# Sheet1.net
KiCad netlist of a schematic drawn in Altium Designer
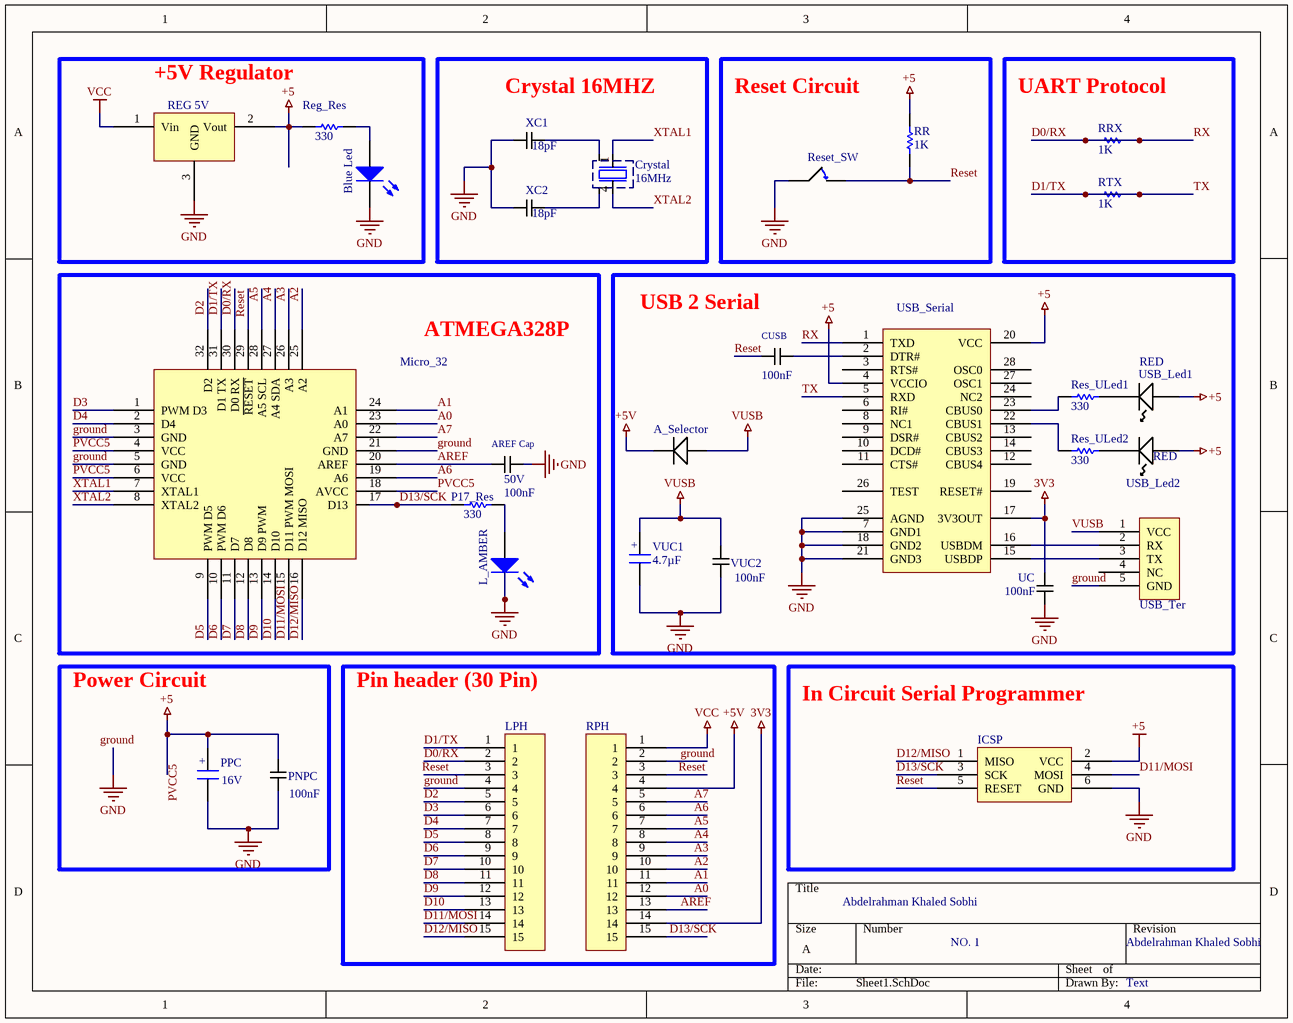
[diagram p0: Sheet1.SchDoc]

(export (version "E")
  (design (tool "Eeschema 10.0.6"))
  (components
    (comp (ref "AREF Cap")
      (value "100nF Ceramic Multilayer Capacitor_1")
      (footprint "CAPCP2012X09N")
      (description "AVX 0805 Standard 100nF Ceramic Multilayer Capacitor, 50 V dc X7R Dielectric ±10% SMD")
      (fields
        (field (name "MANUFACTURER") "AVX")
        (field (name "VOLTAGE") "50V")
        (field (name "CAPACITANCE") "100nF")
        (field (name "CREATOR") "Ritesh Kanjee")
      )
      (libsource (lib "RS Components - Capacitors") (part "100nF Ceramic Multilayer Capacitor_1"))
    )
    (comp (ref "A_Selector")
      (value "Panasonic DB2J20900L Schottky Diode, 0.5A, 20V, 2.4ns, 2-Pin SMini2 F5 B")
      (footprint "DIOM1712X07N")
      (fields
        (field (name "MANUFACTURER") "Panasonic")
        (field (name "MANUFACTURER PART NO.") "DB2J20900L")
        (field (name "CREATED BY") "R Kanjee")
      )
      (libsource (lib "Panasonic Diodes") (part "Schottky Diode, 0.5A, 20V, 2.4ns, 2-Pin SMini2 F5 B"))
    )
    (comp (ref "Blue Led")
      (value "Light-Emitting Diode")
      (libsource (lib "Simulation Generic Components") (part "LED"))
    )
    (comp (ref "Crystal")
      (value "16MHz")
      (footprint "Aker S5C Crystal")
      (description "Aker S5C SMT Crystal")
      (fields
        (field (name "MANUFACTURER") "Aker")
        (field (name "MANUFACTURER PART #") "C5S-16.000-12-3030-X")
        (field (name "CREATOR") "R Kanjee")
      )
      (libsource (lib "Aker Crystals") (part "Aker  C5S-16.000-12-3030-X"))
    )
    (comp (ref "CUSB")
      (value "100nF Ceramic Multilayer Capacitor_1")
      (footprint "CAPCP2012X09N")
      (description "AVX 0805 Standard 100nF Ceramic Multilayer Capacitor, 50 V dc X7R Dielectric ±10% SMD")
      (fields
        (field (name "MANUFACTURER") "AVX")
        (field (name "VOLTAGE") "50V")
        (field (name "CAPACITANCE") "100nF")
        (field (name "CREATOR") "Ritesh Kanjee")
      )
      (libsource (lib "RS Components - Capacitors") (part "100nF Ceramic Multilayer Capacitor_1"))
    )
    (comp (ref "ICSP")
      (value "Programming Headers Dual Row")
      (footprint "ISP HEADER")
      (fields
        (field (name "MANUFACTURER") "FCI")
        (field (name "MANUFACTURER PART NO.") "68000-236HLF")
        (field (name "CREATED BY") "R Kanjee")
      )
      (libsource (lib "PCB Headers") (part "Programming ISP, Programming Headers Dual Row"))
    )
    (comp (ref "LPH")
      (value "connector;str header;single row;.1 cont centers;.095 tail;gold or gtx;36 contact")
      (footprint "Header")
      (fields
        (field (name "MANUFACTURER") "FCI")
        (field (name "MANUFACTURER PART NO.") "68000-236HLF")
        (field (name "CREATED BY") "R Kanjee")
      )
      (libsource (lib "") (part "Single row; PCB headers_1"))
    )
    (comp (ref "L_AMBER")
      (value "Light-Emitting Diode")
      (libsource (lib "Simulation Generic Components") (part "LED"))
    )
    (comp (ref "Micro_32")
      (value "~")
      (footprint "TQFP80P900X900X120-32N")
      (description "ATMEGA328P-AU, 8 bit AVR Microcontroller 20MHz 1 kB, 32 kB Flash, 2 kB RAM, I2C 32-Pin TQFP")
      (fields (field (name "CREATED BY") "Ritesh Kanjee"))
      (libsource (lib "Atmel Microcontrollers") (part "ATMEGA328P-AU"))
    )
    (comp (ref "P17_Res")
      (value "330")
      (description "Resistor")
      (libsource (lib "Simulation Generic Components") (part "Resistor"))
    )
    (comp (ref "PNPC")
      (value "100nF Ceramic Multilayer Capacitor_1")
      (footprint "CAPCP2012X09N")
      (description "AVX 0805 Standard 100nF Ceramic Multilayer Capacitor, 50 V dc X7R Dielectric ±10% SMD")
      (fields
        (field (name "MANUFACTURER") "AVX")
        (field (name "VOLTAGE") "50V")
        (field (name "CAPACITANCE") "100nF")
        (field (name "CREATOR") "Ritesh Kanjee")
      )
      (libsource (lib "RS Components - Capacitors") (part "100nF Ceramic Multilayer Capacitor_1"))
    )
    (comp (ref "PPC")
      (value "Capacitor SMT Tantalum")
      (footprint "CASE A - 3216X18")
      (description "Capacitor,tantalum,SMT,16V,4.7uF,10%,A-case")
      (fields
        (field (name "TOLERANCE") "10%")
        (field (name "VOLTAGE") "16V")
        (field (name "PUBLISHER") "DPSS")
      )
      (libsource (lib "RS Components - Capacitors") (part "4.7µF Tant RS 496-3545"))
    )
    (comp (ref "REG 5V")
      (value "~")
      (footprint "SOT230P700X180-4N")
      (description "LM1117MP-5.0/NOPB, Low Dropout Voltage Regulator, 1.5A, 5 V ±1%, 4-Pin SOT-223")
      (fields (field (name "MANUFACTURER") "Texas Instruments") (field (name "CREATED BY") "R Kanjee"))
      (libsource (lib "TI Low Dropout Voltage Regulator") (part "LM1117MP-5.0"))
    )
    (comp (ref "Reg_Res")
      (value "330")
      (description "Resistor")
      (libsource (lib "Simulation Generic Components") (part "Resistor"))
    )
    (comp (ref "Reset_SW")
      (value "~")
      (footprint "Tactile Switch")
      (description "Tactile Switch SPST- NO 0.05A @24V")
      (fields
        (field (name "MANUFACTURER") "Omron")
        (field (name "MANUFACTURER PART NO.") "B3F1000")
        (field (name "CREATOR") "R Kanjee")
      )
      (libsource (lib "Omron Tactile Switches") (part "Tactile Switch SPST- NO 0.05A @24V"))
    )
    (comp (ref "Res_ULed1")
      (value "330")
      (description "Resistor")
      (libsource (lib "Simulation Generic Components") (part "Resistor"))
    )
    (comp (ref "Res_ULed2")
      (value "330")
      (description "Resistor")
      (libsource (lib "Simulation Generic Components") (part "Resistor"))
    )
    (comp (ref "RPH")
      (value "connector;str header;single row;.1 cont centers;.095 tail;gold or gtx;36 contact")
      (footprint "Header")
      (fields
        (field (name "MANUFACTURER") "FCI")
        (field (name "MANUFACTURER PART NO.") "68000-236HLF")
        (field (name "CREATED BY") "R Kanjee")
      )
      (libsource (lib "PCB Headers") (part "Single row; PCB headers"))
    )
    (comp (ref "RR")
      (value "1K")
      (description "Resistor")
      (libsource (lib "Simulation Generic Components") (part "Resistor"))
    )
    (comp (ref "RRX")
      (value "1K")
      (description "Resistor")
      (libsource (lib "Simulation Generic Components") (part "Resistor"))
    )
    (comp (ref "RTX")
      (value "1K")
      (description "Resistor")
      (libsource (lib "Simulation Generic Components") (part "Resistor"))
    )
    (comp (ref "UC")
      (value "100nF Ceramic Multilayer Capacitor_1")
      (footprint "CAPCP2012X09N")
      (description "AVX 0805 Standard 100nF Ceramic Multilayer Capacitor, 50 V dc X7R Dielectric ±10% SMD")
      (fields
        (field (name "MANUFACTURER") "AVX")
        (field (name "VOLTAGE") "50V")
        (field (name "CAPACITANCE") "100nF")
        (field (name "CREATOR") "Ritesh Kanjee")
      )
      (libsource (lib "RS Components - Capacitors") (part "100nF Ceramic Multilayer Capacitor_1"))
    )
    (comp (ref "USB_Led1")
      (value "Kingbright Red LED, 100 mcd 120 ° 0805")
      (footprint "LED1913X12NRED")
      (fields
        (field (name "MANUFACTURER") "KingBright")
        (field (name "MANUFACTURER PART NO.") "KP-2012SRC-PRV")
        (field (name "COLOR") "RED")
        (field (name "CREATOR") "Ritesh Kanjee")
      )
      (libsource (lib "KingBright LEDs") (part "Kingbright Red LED, 100 mcd 120 ° 0805"))
    )
    (comp (ref "USB_Led2")
      (value "Kingbright Red LED, 100 mcd 120 ° 0805")
      (footprint "LED1913X12NRED")
      (fields
        (field (name "MANUFACTURER") "KingBright")
        (field (name "MANUFACTURER PART NO.") "KP-2012SRC-PRV")
        (field (name "COLOR") "RED")
        (field (name "CREATOR") "Ritesh Kanjee")
      )
      (libsource (lib "KingBright LEDs") (part "Kingbright Red LED, 100 mcd 120 ° 0805"))
    )
    (comp (ref "USB_Serial")
      (value "FT232RL, Universal Asynchronous Receiver & Transmitter 3MBd, 28-Pin, SSOP")
      (footprint "SOP65P780X200-28N")
      (fields
        (field (name "MANUFACTURER PART NO.") "FT232RL")
        (field (name "MANUFACTURER") "FTDI Chip")
        (field (name "CREATOR") "R Kanjee")
      )
      (libsource (lib "FTDI RS232toUSB") (part "FT232RL USB to UART, Universal Asynchronous Receiver & Transmitter 3MBd, 28-Pin, SSOP"))
    )
    (comp (ref "USB_Ter")
      (value "NewMolex Right Angle SMT Female Type B Micro USB Connector, 30 V ac, 1.8A")
      (footprint "MicroUSB")
      (fields
        (field (name "MANUFACTURER") "Molex")
        (field (name "MANUFACTURER PART NO.") "105017-0001")
        (field (name "CREATOR") "R Kanjee")
      )
      (libsource (lib "Molex Connectors") (part "Micro USB Connector, 30 V ac, 1.8A"))
    )
    (comp (ref "VUC1")
      (value "4.7µF")
      (footprint "CASE A - 3216X18")
      (description "Capacitor,tantalum,SMT,16V,4.7uF,10%,A-case")
      (fields
        (field (name "TOLERANCE") "10%")
        (field (name "VOLTAGE") "16V")
        (field (name "PUBLISHER") "DPSS")
      )
      (libsource (lib "RS Components - Capacitors") (part "4.7µF Tant RS 496-3545"))
    )
    (comp (ref "VUC2")
      (value "100nF Ceramic Multilayer Capacitor_1")
      (footprint "CAPCP2012X09N")
      (description "AVX 0805 Standard 100nF Ceramic Multilayer Capacitor, 50 V dc X7R Dielectric ±10% SMD")
      (fields
        (field (name "MANUFACTURER") "AVX")
        (field (name "VOLTAGE") "50V")
        (field (name "CAPACITANCE") "100nF")
        (field (name "CREATOR") "Ritesh Kanjee")
      )
      (libsource (lib "RS Components - Capacitors") (part "100nF Ceramic Multilayer Capacitor_1"))
    )
    (comp (ref "XC1")
      (value "C0805C180J5GACTU")
      (footprint "CAPCP2012X09N")
      (description "18pF Ceramic Multilayer Capacitor, 50 V dc C0G Dielectric ±5% SMD")
      (fields
        (field (name "MANUFACTURER") "Kemet")
        (field (name "VOLTAGE") "50V")
        (field (name "CAPACITANCE") "18pF")
        (field (name "CREATOR") "Ritesh Kanjee")
      )
      (libsource (lib "RS Components - Capacitors") (part "18pF Ceramic Multilayer Capacitor, 50 V dc C0G Dielectric ±5% SMD"))
    )
    (comp (ref "XC2")
      (value "C0805C180J5GACTU")
      (footprint "CAPCP2012X09N")
      (description "18pF Ceramic Multilayer Capacitor, 50 V dc C0G Dielectric ±5% SMD")
      (fields
        (field (name "MANUFACTURER") "Kemet")
        (field (name "VOLTAGE") "50V")
        (field (name "CAPACITANCE") "18pF")
        (field (name "CREATOR") "Ritesh Kanjee")
      )
      (libsource (lib "RS Components - Capacitors") (part "18pF Ceramic Multilayer Capacitor, 50 V dc C0G Dielectric ±5% SMD"))
    )
  )
  (nets
    (net (code "1") (name "+5") (class "Default")
      (node (ref "ICSP") (pin "2") (pinfunction "VCC_2") (pintype "passive"))
      (node (ref "PNPC") (pin "2") (pinfunction "2_2") (pintype "passive"))
      (node (ref "PPC") (pin "1") (pinfunction "1_1") (pintype "passive"))
      (node (ref "REG 5V") (pin "2") (pinfunction "Vout_2") (pintype "passive"))
      (node (ref "RR") (pin "2") (pinfunction "2_2") (pintype "passive"))
      (node (ref "Reg_Res") (pin "1") (pinfunction "1_1") (pintype "passive"))
      (node (ref "USB_Led1") (pin "1") (pinfunction "A_1") (pintype "passive"))
      (node (ref "USB_Led2") (pin "1") (pinfunction "A_1") (pintype "passive"))
      (node (ref "USB_Serial") (pin "20") (pinfunction "VCC_20") (pintype "passive"))
      (node (ref "USB_Serial") (pin "4") (pinfunction "VCCIO_4") (pintype "passive"))
    )
    (net (code "2") (name "+5V") (class "Default")
      (node (ref "A_Selector") (pin "1") (pinfunction "1_1") (pintype "passive"))
      (node (ref "RPH") (pin "4") (pinfunction "4_4") (pintype "passive"))
    )
    (net (code "3") (name "/A0") (class "Default")
      (node (ref "Micro_32") (pin "23") (pinfunction "A0_23") (pintype "passive"))
      (node (ref "RPH") (pin "12") (pinfunction "12_12") (pintype "passive"))
    )
    (net (code "4") (name "/A1") (class "Default")
      (node (ref "Micro_32") (pin "24") (pinfunction "A1_24") (pintype "passive"))
      (node (ref "RPH") (pin "11") (pinfunction "11_11") (pintype "passive"))
    )
    (net (code "5") (name "/A2") (class "Default")
      (node (ref "Micro_32") (pin "25") (pinfunction "A2_25") (pintype "passive"))
      (node (ref "RPH") (pin "10") (pinfunction "10_10") (pintype "passive"))
    )
    (net (code "6") (name "/A3") (class "Default")
      (node (ref "Micro_32") (pin "26") (pinfunction "A3_26") (pintype "passive"))
      (node (ref "RPH") (pin "9") (pinfunction "9_9") (pintype "passive"))
    )
    (net (code "7") (name "/A4") (class "Default")
      (node (ref "Micro_32") (pin "27") (pinfunction "A4_SDA_27") (pintype "passive"))
      (node (ref "RPH") (pin "8") (pinfunction "8_8") (pintype "passive"))
    )
    (net (code "8") (name "/A5") (class "Default")
      (node (ref "Micro_32") (pin "28") (pinfunction "A5_SCL_28") (pintype "passive"))
      (node (ref "RPH") (pin "7") (pinfunction "7_7") (pintype "passive"))
    )
    (net (code "9") (name "/A6") (class "Default")
      (node (ref "Micro_32") (pin "19") (pinfunction "A6_19") (pintype "passive"))
      (node (ref "RPH") (pin "6") (pinfunction "6_6") (pintype "passive"))
    )
    (net (code "10") (name "/A7") (class "Default")
      (node (ref "Micro_32") (pin "22") (pinfunction "A7_22") (pintype "passive"))
      (node (ref "RPH") (pin "5") (pinfunction "5_5") (pintype "passive"))
    )
    (net (code "11") (name "/AREF") (class "Default")
      (node (ref "AREF Cap") (pin "1") (pinfunction "1_1") (pintype "passive"))
      (node (ref "Micro_32") (pin "20") (pinfunction "AREF_20") (pintype "passive"))
      (node (ref "RPH") (pin "13") (pinfunction "13_13") (pintype "passive"))
    )
    (net (code "12") (name "/D0{slash}RX") (class "Default")
      (node (ref "LPH") (pin "2") (pinfunction "2_2") (pintype "passive"))
      (node (ref "Micro_32") (pin "30") (pinfunction "D0_RX_30") (pintype "passive"))
      (node (ref "RRX") (pin "1") (pinfunction "1_1") (pintype "passive"))
      (node (ref "RRX") (pin "2") (pinfunction "2_2") (pintype "passive"))
      (node (ref "USB_Serial") (pin "1") (pinfunction "TXD_1") (pintype "passive"))
    )
    (net (code "13") (name "/D1{slash}TX") (class "Default")
      (node (ref "LPH") (pin "1") (pinfunction "1_1") (pintype "passive"))
      (node (ref "Micro_32") (pin "31") (pinfunction "D1_TX_31") (pintype "passive"))
      (node (ref "RTX") (pin "1") (pinfunction "1_1") (pintype "passive"))
      (node (ref "RTX") (pin "2") (pinfunction "2_2") (pintype "passive"))
      (node (ref "USB_Serial") (pin "5") (pinfunction "RXD_5") (pintype "passive"))
    )
    (net (code "14") (name "/D2") (class "Default")
      (node (ref "LPH") (pin "5") (pinfunction "5_5") (pintype "passive"))
      (node (ref "Micro_32") (pin "32") (pinfunction "D2_32") (pintype "passive"))
    )
    (net (code "15") (name "/D3") (class "Default")
      (node (ref "LPH") (pin "6") (pinfunction "6_6") (pintype "passive"))
      (node (ref "Micro_32") (pin "1") (pinfunction "PWM_D3_1") (pintype "passive"))
    )
    (net (code "16") (name "/D4") (class "Default")
      (node (ref "LPH") (pin "7") (pinfunction "7_7") (pintype "passive"))
      (node (ref "Micro_32") (pin "2") (pinfunction "D4_2") (pintype "passive"))
    )
    (net (code "17") (name "/D5") (class "Default")
      (node (ref "LPH") (pin "8") (pinfunction "8_8") (pintype "passive"))
      (node (ref "Micro_32") (pin "9") (pinfunction "PWM_D5_9") (pintype "passive"))
    )
    (net (code "18") (name "/D6") (class "Default")
      (node (ref "LPH") (pin "9") (pinfunction "9_9") (pintype "passive"))
      (node (ref "Micro_32") (pin "10") (pinfunction "PWM_D6_10") (pintype "passive"))
    )
    (net (code "19") (name "/D7") (class "Default")
      (node (ref "LPH") (pin "10") (pinfunction "10_10") (pintype "passive"))
      (node (ref "Micro_32") (pin "11") (pinfunction "D7_11") (pintype "passive"))
    )
    (net (code "20") (name "/D8") (class "Default")
      (node (ref "LPH") (pin "11") (pinfunction "11_11") (pintype "passive"))
      (node (ref "Micro_32") (pin "12") (pinfunction "D8_12") (pintype "passive"))
    )
    (net (code "21") (name "/D9") (class "Default")
      (node (ref "LPH") (pin "12") (pinfunction "12_12") (pintype "passive"))
      (node (ref "Micro_32") (pin "13") (pinfunction "D9_PWM_13") (pintype "passive"))
    )
    (net (code "22") (name "/D10") (class "Default")
      (node (ref "LPH") (pin "13") (pinfunction "13_13") (pintype "passive"))
      (node (ref "Micro_32") (pin "14") (pinfunction "D10_14") (pintype "passive"))
    )
    (net (code "23") (name "/D11{slash}MOSI") (class "Default")
      (node (ref "ICSP") (pin "4") (pinfunction "MOSI_4") (pintype "passive"))
      (node (ref "LPH") (pin "14") (pinfunction "14_14") (pintype "passive"))
      (node (ref "Micro_32") (pin "15") (pinfunction "D11_PWM_MOSI_15") (pintype "passive"))
    )
    (net (code "24") (name "/D12{slash}MISO") (class "Default")
      (node (ref "ICSP") (pin "1") (pinfunction "MISO_1") (pintype "passive"))
      (node (ref "LPH") (pin "15") (pinfunction "15_15") (pintype "passive"))
      (node (ref "Micro_32") (pin "16") (pinfunction "D12_MISO_16") (pintype "passive"))
    )
    (net (code "25") (name "/D13{slash}SCK") (class "Default")
      (node (ref "ICSP") (pin "3") (pinfunction "SCK_3") (pintype "passive"))
      (node (ref "Micro_32") (pin "17") (pinfunction "D13_17") (pintype "passive"))
      (node (ref "P17_Res") (pin "1") (pinfunction "1_1") (pintype "passive"))
      (node (ref "RPH") (pin "15") (pinfunction "15_15") (pintype "passive"))
    )
    (net (code "26") (name "/PVCC5") (class "Default")
      (node (ref "Micro_32") (pin "18") (pinfunction "AVCC_18") (pintype "passive"))
      (node (ref "Micro_32") (pin "4") (pinfunction "VCC_4") (pintype "passive"))
      (node (ref "Micro_32") (pin "6") (pinfunction "VCC_6") (pintype "passive"))
    )
    (net (code "27") (name "/Reset") (class "Default")
      (node (ref "CUSB") (pin "1") (pinfunction "1_1") (pintype "passive"))
      (node (ref "ICSP") (pin "5") (pinfunction "RESET_5") (pintype "passive"))
      (node (ref "LPH") (pin "3") (pinfunction "3_3") (pintype "passive"))
      (node (ref "Micro_32") (pin "29") (pinfunction "~{RESET}_29") (pintype "passive"))
      (node (ref "RPH") (pin "3") (pinfunction "3_3") (pintype "passive"))
      (node (ref "RR") (pin "1") (pinfunction "1_1") (pintype "passive"))
      (node (ref "Reset_SW") (pin "1") (pinfunction "1_1") (pintype "passive"))
    )
    (net (code "28") (name "/XTAL1") (class "Default")
      (node (ref "Crystal") (pin "1") (pinfunction "1_1") (pintype "passive"))
      (node (ref "Micro_32") (pin "7") (pinfunction "XTAL1_7") (pintype "passive"))
    )
    (net (code "29") (name "/XTAL2") (class "Default")
      (node (ref "Crystal") (pin "4") (pinfunction "4_4") (pintype "passive"))
      (node (ref "Micro_32") (pin "8") (pinfunction "XTAL2_8") (pintype "passive"))
    )
    (net (code "30") (name "/ground") (class "Default")
      (node (ref "LPH") (pin "4") (pinfunction "4_4") (pintype "passive"))
      (node (ref "Micro_32") (pin "21") (pinfunction "GND_21") (pintype "passive"))
      (node (ref "Micro_32") (pin "3") (pinfunction "GND_3") (pintype "passive"))
      (node (ref "Micro_32") (pin "5") (pinfunction "GND_5") (pintype "passive"))
      (node (ref "RPH") (pin "2") (pinfunction "2_2") (pintype "passive"))
      (node (ref "USB_Ter") (pin "5") (pinfunction "GND_5") (pintype "passive"))
    )
    (net (code "31") (name "3V3") (class "Default")
      (node (ref "RPH") (pin "14") (pinfunction "14_14") (pintype "passive"))
      (node (ref "UC") (pin "2") (pinfunction "2_2") (pintype "passive"))
      (node (ref "USB_Serial") (pin "17") (pinfunction "3V3OUT_17") (pintype "passive"))
    )
    (net (code "32") (name "GND") (class "Default")
      (node (ref "AREF Cap") (pin "2") (pinfunction "2_2") (pintype "passive"))
      (node (ref "Blue Led") (pin "2") (pinfunction "K_2") (pintype "passive"))
      (node (ref "ICSP") (pin "6") (pinfunction "GND_6") (pintype "passive"))
      (node (ref "L_AMBER") (pin "2") (pinfunction "K_2") (pintype "passive"))
      (node (ref "PNPC") (pin "1") (pinfunction "1_1") (pintype "passive"))
      (node (ref "PPC") (pin "2") (pinfunction "2_2") (pintype "passive"))
      (node (ref "REG 5V") (pin "3") (pinfunction "GND_3") (pintype "passive"))
      (node (ref "Reset_SW") (pin "1") (pinfunction "1_1") (pintype "passive"))
      (node (ref "UC") (pin "1") (pinfunction "1_1") (pintype "passive"))
      (node (ref "USB_Serial") (pin "18") (pinfunction "GND2_18") (pintype "passive"))
      (node (ref "USB_Serial") (pin "21") (pinfunction "GND3_21") (pintype "passive"))
      (node (ref "USB_Serial") (pin "25") (pinfunction "AGND_25") (pintype "passive"))
      (node (ref "USB_Serial") (pin "7") (pinfunction "GND1_7") (pintype "passive"))
      (node (ref "VUC1") (pin "2") (pinfunction "2_2") (pintype "passive"))
      (node (ref "VUC2") (pin "1") (pinfunction "1_1") (pintype "passive"))
      (node (ref "XC1") (pin "1") (pinfunction "1_1") (pintype "passive"))
      (node (ref "XC2") (pin "1") (pinfunction "1_1") (pintype "passive"))
    )
    (net (code "33") (name "Net-(Blue Led-A)") (class "Default")
      (node (ref "Blue Led") (pin "1") (pinfunction "A_1") (pintype "passive"))
      (node (ref "Reg_Res") (pin "2") (pinfunction "2_2") (pintype "passive"))
    )
    (net (code "34") (name "Net-(Crystal-Gnd-Pad2)") (class "Default")
      (node (ref "Crystal") (pin "2") (pinfunction "Gnd_2") (pintype "power_in"))
      (node (ref "XC2") (pin "2") (pinfunction "2_2") (pintype "passive"))
    )
    (net (code "35") (name "Net-(Crystal-Gnd-Pad3)") (class "Default")
      (node (ref "Crystal") (pin "3") (pinfunction "Gnd_3") (pintype "power_in"))
      (node (ref "XC1") (pin "2") (pinfunction "2_2") (pintype "passive"))
    )
    (net (code "36") (name "Net-(L_AMBER-A)") (class "Default")
      (node (ref "L_AMBER") (pin "1") (pinfunction "A_1") (pintype "passive"))
      (node (ref "P17_Res") (pin "2") (pinfunction "2_2") (pintype "passive"))
    )
    (net (code "37") (name "Net-(USB_Led1-K)") (class "Default")
      (node (ref "Res_ULed1") (pin "2") (pinfunction "2_2") (pintype "passive"))
      (node (ref "USB_Led1") (pin "2") (pinfunction "K_2") (pintype "passive"))
    )
    (net (code "38") (name "Net-(USB_Led2-K)") (class "Default")
      (node (ref "Res_ULed2") (pin "2") (pinfunction "2_2") (pintype "passive"))
      (node (ref "USB_Led2") (pin "2") (pinfunction "K_2") (pintype "passive"))
    )
    (net (code "39") (name "Net-(USB_Serial-CBUS0)") (class "Default")
      (node (ref "Res_ULed1") (pin "1") (pinfunction "1_1") (pintype "passive"))
      (node (ref "USB_Serial") (pin "23") (pinfunction "CBUS0_23") (pintype "passive"))
    )
    (net (code "40") (name "Net-(USB_Serial-CBUS1)") (class "Default")
      (node (ref "Res_ULed2") (pin "1") (pinfunction "1_1") (pintype "passive"))
      (node (ref "USB_Serial") (pin "22") (pinfunction "CBUS1_22") (pintype "passive"))
    )
    (net (code "41") (name "Net-(USB_Serial-DTR#)") (class "Default")
      (node (ref "CUSB") (pin "2") (pinfunction "2_2") (pintype "passive"))
      (node (ref "USB_Serial") (pin "2") (pinfunction "DTR#_2") (pintype "passive"))
    )
    (net (code "42") (name "Net-(USB_Serial-USBDM)") (class "Default")
      (node (ref "USB_Serial") (pin "16") (pinfunction "USBDM_16") (pintype "passive"))
      (node (ref "USB_Ter") (pin "2") (pinfunction "RX_2") (pintype "passive"))
    )
    (net (code "43") (name "Net-(USB_Serial-USBDP)") (class "Default")
      (node (ref "USB_Serial") (pin "15") (pinfunction "USBDP_15") (pintype "passive"))
      (node (ref "USB_Ter") (pin "3") (pinfunction "TX_3") (pintype "passive"))
    )
    (net (code "44") (name "VCC") (class "Default")
      (node (ref "REG 5V") (pin "1") (pinfunction "Vin_1") (pintype "passive"))
      (node (ref "RPH") (pin "1") (pinfunction "1_1") (pintype "passive"))
    )
    (net (code "45") (name "VUSB") (class "Default")
      (node (ref "A_Selector") (pin "2") (pinfunction "2_2") (pintype "passive"))
      (node (ref "USB_Ter") (pin "1") (pinfunction "VCC_1") (pintype "passive"))
      (node (ref "VUC1") (pin "1") (pinfunction "1_1") (pintype "passive"))
      (node (ref "VUC2") (pin "2") (pinfunction "2_2") (pintype "passive"))
    )
    (net (code "46") (name "unconnected-(USB_Serial-CBUS2-Pad13)") (class "Default")
      (node (ref "USB_Serial") (pin "13") (pinfunction "CBUS2_13") (pintype "passive"))
    )
    (net (code "47") (name "unconnected-(USB_Serial-CBUS3-Pad14)") (class "Default")
      (node (ref "USB_Serial") (pin "14") (pinfunction "CBUS3_14") (pintype "passive"))
    )
    (net (code "48") (name "unconnected-(USB_Serial-CBUS4-Pad12)") (class "Default")
      (node (ref "USB_Serial") (pin "12") (pinfunction "CBUS4_12") (pintype "passive"))
    )
    (net (code "49") (name "unconnected-(USB_Serial-CTS#-Pad11)") (class "Default")
      (node (ref "USB_Serial") (pin "11") (pinfunction "CTS#_11") (pintype "passive"))
    )
    (net (code "50") (name "unconnected-(USB_Serial-DCD#-Pad10)") (class "Default")
      (node (ref "USB_Serial") (pin "10") (pinfunction "DCD#_10") (pintype "passive"))
    )
    (net (code "51") (name "unconnected-(USB_Serial-DSR#-Pad9)") (class "Default")
      (node (ref "USB_Serial") (pin "9") (pinfunction "DSR#_9") (pintype "passive"))
    )
    (net (code "52") (name "unconnected-(USB_Serial-NC1-Pad8)") (class "Default")
      (node (ref "USB_Serial") (pin "8") (pinfunction "NC1_8") (pintype "passive"))
    )
    (net (code "53") (name "unconnected-(USB_Serial-NC2-Pad24)") (class "Default")
      (node (ref "USB_Serial") (pin "24") (pinfunction "NC2_24") (pintype "passive"))
    )
    (net (code "54") (name "unconnected-(USB_Serial-OSC0-Pad28)") (class "Default")
      (node (ref "USB_Serial") (pin "28") (pinfunction "OSC0_28") (pintype "passive"))
    )
    (net (code "55") (name "unconnected-(USB_Serial-OSC1-Pad27)") (class "Default")
      (node (ref "USB_Serial") (pin "27") (pinfunction "OSC1_27") (pintype "passive"))
    )
    (net (code "56") (name "unconnected-(USB_Serial-RESET#-Pad19)") (class "Default")
      (node (ref "USB_Serial") (pin "19") (pinfunction "RESET#_19") (pintype "passive"))
    )
    (net (code "57") (name "unconnected-(USB_Serial-RI#-Pad6)") (class "Default")
      (node (ref "USB_Serial") (pin "6") (pinfunction "RI#_6") (pintype "passive"))
    )
    (net (code "58") (name "unconnected-(USB_Serial-RTS#-Pad3)") (class "Default")
      (node (ref "USB_Serial") (pin "3") (pinfunction "RTS#_3") (pintype "passive"))
    )
    (net (code "59") (name "unconnected-(USB_Serial-TEST-Pad26)") (class "Default")
      (node (ref "USB_Serial") (pin "26") (pinfunction "TEST_26") (pintype "passive"))
    )
    (net (code "60") (name "unconnected-(USB_Ter-NC-Pad4)") (class "Default")
      (node (ref "USB_Ter") (pin "4") (pinfunction "NC_4") (pintype "passive"))
    )
  )
)
